# Voltmetr_MEZ.net
KiCad netlist of a schematic drawn in Altium Designer
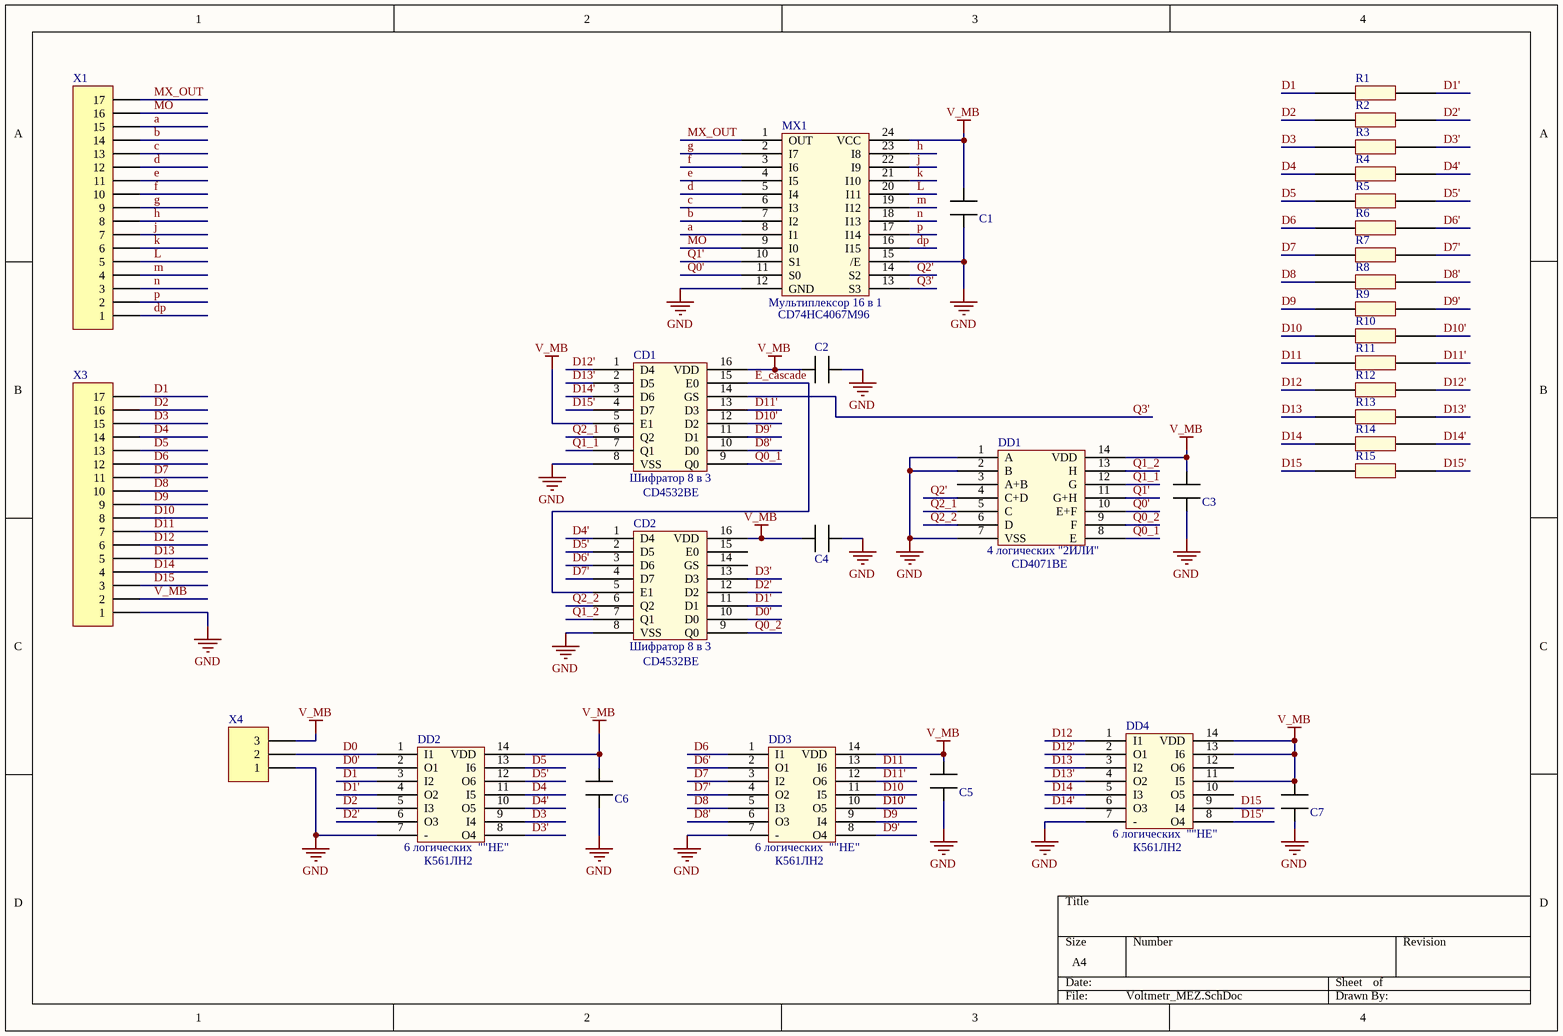
[diagram p0: Voltmetr_MEZ.SchDoc]

(export (version "E")
  (design (tool "Eeschema 10.0.6"))
  (components
    (comp (ref "C1")
      (value "CAP_SMALL")
      (footprint "CAP_SMALL")
      (libsource (lib "vpl_Schlib") (part "CAP_SMALL"))
    )
    (comp (ref "C2")
      (value "CAP_SMALL")
      (footprint "CAP_SMALL")
      (libsource (lib "vpl_Schlib") (part "CAP_SMALL"))
    )
    (comp (ref "C3")
      (value "CAP_SMALL")
      (footprint "CAP_SMALL")
      (libsource (lib "vpl_Schlib") (part "CAP_SMALL"))
    )
    (comp (ref "C4")
      (value "CAP_SMALL")
      (footprint "CAP_SMALL")
      (libsource (lib "vpl_Schlib") (part "CAP_SMALL"))
    )
    (comp (ref "C5")
      (value "CAP_SMALL")
      (footprint "CAP_SMALL")
      (libsource (lib "vpl_Schlib") (part "CAP_SMALL"))
    )
    (comp (ref "C6")
      (value "CAP_SMALL")
      (footprint "CAP_SMALL")
      (libsource (lib "vpl_Schlib") (part "CAP_SMALL"))
    )
    (comp (ref "C7")
      (value "CAP_SMALL")
      (footprint "CAP_SMALL")
      (libsource (lib "vpl_Schlib") (part "CAP_SMALL"))
    )
    (comp (ref "CD1")
      (value "CD4532BE")
      (footprint "DIP16_PANNEL")
      (description "Шифратор приоритетный 8 - 3 [DIP-16]")
      (libsource (lib "msp_SchLib") (part "CD4532BE"))
    )
    (comp (ref "CD2")
      (value "CD4532BE")
      (footprint "DIP16_PANNEL")
      (description "Шифратор приоритетный 8 - 3 [DIP-16]")
      (libsource (lib "msp_SchLib") (part "CD4532BE"))
    )
    (comp (ref "DD1")
      (value "CD4071BE")
      (footprint "Dip14_pannel")
      (description "Четыре логических элемента \"2ИЛИ\", [DIP-14]")
      (libsource (lib "msp_SchLib") (part "CD4071BE"))
    )
    (comp (ref "DD2")
      (value "К561ЛН2")
      (footprint "Dip14_pannel")
      (description "Шесть логических элементов \"HЕ\" (DIP-14)")
      (libsource (lib "msp_SchLib") (part "К561ЛН2"))
    )
    (comp (ref "DD3")
      (value "К561ЛН2")
      (footprint "Dip14_pannel")
      (description "Шесть логических элементов \"HЕ\" (DIP-14)")
      (libsource (lib "msp_SchLib") (part "К561ЛН2"))
    )
    (comp (ref "DD4")
      (value "К561ЛН2")
      (footprint "Dip14_pannel")
      (description "Шесть логических элементов \"HЕ\" (DIP-14)")
      (libsource (lib "msp_SchLib") (part "К561ЛН2"))
    )
    (comp (ref "MX1")
      (value "CD74HC4067M96")
      (footprint "SOIC-24")
      (description "16-и канальный аналоговый мультиплексор/ демультиплексор, [SO-24]")
      (libsource (lib "msp_SchLib") (part "CD74HC4067M96"))
    )
    (comp (ref "R1") (value "resistor") (footprint "RES 0805") (libsource (lib "msp_SchLib") (part "RES")))
    (comp (ref "R2") (value "resistor") (footprint "RES 0805") (libsource (lib "msp_SchLib") (part "RES")))
    (comp (ref "R3") (value "resistor") (footprint "RES 0805") (libsource (lib "msp_SchLib") (part "RES")))
    (comp (ref "R4") (value "resistor") (footprint "RES 0805") (libsource (lib "msp_SchLib") (part "RES")))
    (comp (ref "R5") (value "resistor") (footprint "RES 0805") (libsource (lib "msp_SchLib") (part "RES")))
    (comp (ref "R6") (value "resistor") (footprint "RES 0805") (libsource (lib "msp_SchLib") (part "RES")))
    (comp (ref "R7") (value "resistor") (footprint "RES 0805") (libsource (lib "msp_SchLib") (part "RES")))
    (comp (ref "R8") (value "resistor") (footprint "RES 0805") (libsource (lib "msp_SchLib") (part "RES")))
    (comp (ref "R9") (value "resistor") (footprint "RES 0805") (libsource (lib "msp_SchLib") (part "RES")))
    (comp (ref "R10") (value "resistor") (footprint "RES 0805") (libsource (lib "msp_SchLib") (part "RES")))
    (comp (ref "R11") (value "resistor") (footprint "RES 0805") (libsource (lib "msp_SchLib") (part "RES")))
    (comp (ref "R12") (value "resistor") (footprint "RES 0805") (libsource (lib "msp_SchLib") (part "RES")))
    (comp (ref "R13") (value "resistor") (footprint "RES 0805") (libsource (lib "msp_SchLib") (part "RES")))
    (comp (ref "R14") (value "resistor") (footprint "RES 0805") (libsource (lib "msp_SchLib") (part "RES")))
    (comp (ref "R15") (value "resistor") (footprint "RES 0805") (libsource (lib "msp_SchLib") (part "RES")))
    (comp (ref "X1")
      (value "Header 17")
      (footprint "HDR1X17")
      (description "Header, 17-Pin")
      (fields (field (name "PUBLISHER") "Altium Limited"))
      (libsource (lib "Miscellaneous Connectors") (part "Header 17"))
    )
    (comp (ref "X3")
      (value "Header 17")
      (footprint "HDR1X17")
      (description "Header, 17-Pin")
      (fields (field (name "PUBLISHER") "Altium Limited"))
      (libsource (lib "Miscellaneous Connectors") (part "Header 17"))
    )
    (comp (ref "X4")
      (value "Header 3")
      (footprint "HDR1X3")
      (description "Header, 3-Pin")
      (fields (field (name "PUBLISHER") "Altium Limited"))
      (libsource (lib "Miscellaneous Connectors") (part "Header 3"))
    )
  )
  (nets
    (net (code "2") (name "/D0") (class "Default")
      (node (ref "DD2") (pin "1") (pinfunction "I1_1") (pintype "passive"))
      (node (ref "X4") (pin "2") (pinfunction "2_2") (pintype "passive"))
    )
    (net (code "3") (name "/D0'") (class "Default")
      (node (ref "CD2") (pin "10") (pinfunction "D0_10") (pintype "passive"))
      (node (ref "DD2") (pin "2") (pinfunction "O1_2") (pintype "passive"))
    )
    (net (code "4") (name "/D1") (class "Default")
      (node (ref "DD2") (pin "3") (pinfunction "I2_3") (pintype "passive"))
      (node (ref "R1") (pin "1") (pinfunction "1_1") (pintype "passive"))
      (node (ref "X3") (pin "17") (pinfunction "17_17") (pintype "passive"))
    )
    (net (code "5") (name "/D1'") (class "Default")
      (node (ref "CD2") (pin "11") (pinfunction "D1_11") (pintype "passive"))
      (node (ref "DD2") (pin "4") (pinfunction "O2_4") (pintype "passive"))
      (node (ref "R1") (pin "2") (pinfunction "2_2") (pintype "passive"))
    )
    (net (code "6") (name "/D2") (class "Default")
      (node (ref "DD2") (pin "5") (pinfunction "I3_5") (pintype "passive"))
      (node (ref "R2") (pin "1") (pinfunction "1_1") (pintype "passive"))
      (node (ref "X3") (pin "16") (pinfunction "16_16") (pintype "passive"))
    )
    (net (code "7") (name "/D2'") (class "Default")
      (node (ref "CD2") (pin "12") (pinfunction "D2_12") (pintype "passive"))
      (node (ref "DD2") (pin "6") (pinfunction "O3_6") (pintype "passive"))
      (node (ref "R2") (pin "2") (pinfunction "2_2") (pintype "passive"))
    )
    (net (code "8") (name "/D3") (class "Default")
      (node (ref "DD2") (pin "9") (pinfunction "I4_9") (pintype "passive"))
      (node (ref "R3") (pin "1") (pinfunction "1_1") (pintype "passive"))
      (node (ref "X3") (pin "15") (pinfunction "15_15") (pintype "passive"))
    )
    (net (code "9") (name "/D3'") (class "Default")
      (node (ref "CD2") (pin "13") (pinfunction "D3_13") (pintype "passive"))
      (node (ref "DD2") (pin "8") (pinfunction "O4_8") (pintype "passive"))
      (node (ref "R3") (pin "2") (pinfunction "2_2") (pintype "passive"))
    )
    (net (code "10") (name "/D4") (class "Default")
      (node (ref "DD2") (pin "11") (pinfunction "I5_11") (pintype "passive"))
      (node (ref "R4") (pin "1") (pinfunction "1_1") (pintype "passive"))
      (node (ref "X3") (pin "14") (pinfunction "14_14") (pintype "passive"))
    )
    (net (code "11") (name "/D4'") (class "Default")
      (node (ref "CD2") (pin "1") (pinfunction "D4_1") (pintype "passive"))
      (node (ref "DD2") (pin "10") (pinfunction "O5_10") (pintype "passive"))
      (node (ref "R4") (pin "2") (pinfunction "2_2") (pintype "passive"))
    )
    (net (code "12") (name "/D5") (class "Default")
      (node (ref "DD2") (pin "13") (pinfunction "I6_13") (pintype "passive"))
      (node (ref "R5") (pin "1") (pinfunction "1_1") (pintype "passive"))
      (node (ref "X3") (pin "13") (pinfunction "13_13") (pintype "passive"))
    )
    (net (code "13") (name "/D5'") (class "Default")
      (node (ref "CD2") (pin "2") (pinfunction "D5_2") (pintype "passive"))
      (node (ref "DD2") (pin "12") (pinfunction "O6_12") (pintype "passive"))
      (node (ref "R5") (pin "2") (pinfunction "2_2") (pintype "passive"))
    )
    (net (code "14") (name "/D6") (class "Default")
      (node (ref "DD3") (pin "1") (pinfunction "I1_1") (pintype "passive"))
      (node (ref "R6") (pin "1") (pinfunction "1_1") (pintype "passive"))
      (node (ref "X3") (pin "12") (pinfunction "12_12") (pintype "passive"))
    )
    (net (code "15") (name "/D6'") (class "Default")
      (node (ref "CD2") (pin "3") (pinfunction "D6_3") (pintype "passive"))
      (node (ref "DD3") (pin "2") (pinfunction "O1_2") (pintype "passive"))
      (node (ref "R6") (pin "2") (pinfunction "2_2") (pintype "passive"))
    )
    (net (code "16") (name "/D7") (class "Default")
      (node (ref "DD3") (pin "3") (pinfunction "I2_3") (pintype "passive"))
      (node (ref "R7") (pin "1") (pinfunction "1_1") (pintype "passive"))
      (node (ref "X3") (pin "11") (pinfunction "11_11") (pintype "passive"))
    )
    (net (code "17") (name "/D7'") (class "Default")
      (node (ref "CD2") (pin "4") (pinfunction "D7_4") (pintype "passive"))
      (node (ref "DD3") (pin "4") (pinfunction "O2_4") (pintype "passive"))
      (node (ref "R7") (pin "2") (pinfunction "2_2") (pintype "passive"))
    )
    (net (code "18") (name "/D8") (class "Default")
      (node (ref "DD3") (pin "5") (pinfunction "I3_5") (pintype "passive"))
      (node (ref "R8") (pin "1") (pinfunction "1_1") (pintype "passive"))
      (node (ref "X3") (pin "10") (pinfunction "10_10") (pintype "passive"))
    )
    (net (code "19") (name "/D8'") (class "Default")
      (node (ref "CD1") (pin "10") (pinfunction "D0_10") (pintype "passive"))
      (node (ref "DD3") (pin "6") (pinfunction "O3_6") (pintype "passive"))
      (node (ref "R8") (pin "2") (pinfunction "2_2") (pintype "passive"))
    )
    (net (code "20") (name "/D9") (class "Default")
      (node (ref "DD3") (pin "9") (pinfunction "I4_9") (pintype "passive"))
      (node (ref "R9") (pin "1") (pinfunction "1_1") (pintype "passive"))
      (node (ref "X3") (pin "9") (pinfunction "9_9") (pintype "passive"))
    )
    (net (code "21") (name "/D9'") (class "Default")
      (node (ref "CD1") (pin "11") (pinfunction "D1_11") (pintype "passive"))
      (node (ref "DD3") (pin "8") (pinfunction "O4_8") (pintype "passive"))
      (node (ref "R9") (pin "2") (pinfunction "2_2") (pintype "passive"))
    )
    (net (code "22") (name "/D10") (class "Default")
      (node (ref "DD3") (pin "11") (pinfunction "I5_11") (pintype "passive"))
      (node (ref "R10") (pin "1") (pinfunction "1_1") (pintype "passive"))
      (node (ref "X3") (pin "8") (pinfunction "8_8") (pintype "passive"))
    )
    (net (code "23") (name "/D10'") (class "Default")
      (node (ref "CD1") (pin "12") (pinfunction "D2_12") (pintype "passive"))
      (node (ref "DD3") (pin "10") (pinfunction "O5_10") (pintype "passive"))
      (node (ref "R10") (pin "2") (pinfunction "2_2") (pintype "passive"))
    )
    (net (code "24") (name "/D11") (class "Default")
      (node (ref "DD3") (pin "13") (pinfunction "I6_13") (pintype "passive"))
      (node (ref "R11") (pin "1") (pinfunction "1_1") (pintype "passive"))
      (node (ref "X3") (pin "7") (pinfunction "7_7") (pintype "passive"))
    )
    (net (code "25") (name "/D11'") (class "Default")
      (node (ref "CD1") (pin "13") (pinfunction "D3_13") (pintype "passive"))
      (node (ref "DD3") (pin "12") (pinfunction "O6_12") (pintype "passive"))
      (node (ref "R11") (pin "2") (pinfunction "2_2") (pintype "passive"))
    )
    (net (code "26") (name "/D12") (class "Default")
      (node (ref "DD4") (pin "1") (pinfunction "I1_1") (pintype "passive"))
      (node (ref "R12") (pin "1") (pinfunction "1_1") (pintype "passive"))
      (node (ref "X3") (pin "6") (pinfunction "6_6") (pintype "passive"))
    )
    (net (code "27") (name "/D12'") (class "Default")
      (node (ref "CD1") (pin "1") (pinfunction "D4_1") (pintype "passive"))
      (node (ref "DD4") (pin "2") (pinfunction "O1_2") (pintype "passive"))
      (node (ref "R12") (pin "2") (pinfunction "2_2") (pintype "passive"))
    )
    (net (code "28") (name "/D13") (class "Default")
      (node (ref "DD4") (pin "3") (pinfunction "I2_3") (pintype "passive"))
      (node (ref "R13") (pin "1") (pinfunction "1_1") (pintype "passive"))
      (node (ref "X3") (pin "5") (pinfunction "5_5") (pintype "passive"))
    )
    (net (code "29") (name "/D13'") (class "Default")
      (node (ref "CD1") (pin "2") (pinfunction "D5_2") (pintype "passive"))
      (node (ref "DD4") (pin "4") (pinfunction "O2_4") (pintype "passive"))
      (node (ref "R13") (pin "2") (pinfunction "2_2") (pintype "passive"))
    )
    (net (code "30") (name "/D14") (class "Default")
      (node (ref "DD4") (pin "5") (pinfunction "I3_5") (pintype "passive"))
      (node (ref "R14") (pin "1") (pinfunction "1_1") (pintype "passive"))
      (node (ref "X3") (pin "4") (pinfunction "4_4") (pintype "passive"))
    )
    (net (code "31") (name "/D14'") (class "Default")
      (node (ref "CD1") (pin "3") (pinfunction "D6_3") (pintype "passive"))
      (node (ref "DD4") (pin "6") (pinfunction "O3_6") (pintype "passive"))
      (node (ref "R14") (pin "2") (pinfunction "2_2") (pintype "passive"))
    )
    (net (code "32") (name "/D15") (class "Default")
      (node (ref "DD4") (pin "9") (pinfunction "I4_9") (pintype "passive"))
      (node (ref "R15") (pin "1") (pinfunction "1_1") (pintype "passive"))
      (node (ref "X3") (pin "3") (pinfunction "3_3") (pintype "passive"))
    )
    (net (code "33") (name "/D15'") (class "Default")
      (node (ref "CD1") (pin "4") (pinfunction "D7_4") (pintype "passive"))
      (node (ref "DD4") (pin "8") (pinfunction "O4_8") (pintype "passive"))
      (node (ref "R15") (pin "2") (pinfunction "2_2") (pintype "passive"))
    )
    (net (code "34") (name "/E_cascade") (class "Default")
      (node (ref "CD1") (pin "15") (pinfunction "E0_15") (pintype "passive"))
      (node (ref "CD2") (pin "5") (pinfunction "E1_5") (pintype "passive"))
    )
    (net (code "35") (name "/L") (class "Default")
      (node (ref "MX1") (pin "20") (pinfunction "I11_20") (pintype "passive"))
      (node (ref "X1") (pin "5") (pinfunction "5_5") (pintype "passive"))
    )
    (net (code "36") (name "/MX_OUT") (class "Default")
      (node (ref "MX1") (pin "1") (pinfunction "OUT_1") (pintype "passive"))
      (node (ref "X1") (pin "17") (pinfunction "17_17") (pintype "passive"))
    )
    (net (code "37") (name "/Q0'") (class "Default")
      (node (ref "DD1") (pin "10") (pinfunction "E+F_10") (pintype "passive"))
      (node (ref "MX1") (pin "11") (pinfunction "S0_11") (pintype "passive"))
    )
    (net (code "38") (name "/Q0_1") (class "Default")
      (node (ref "CD1") (pin "9") (pinfunction "Q0_9") (pintype "passive"))
      (node (ref "DD1") (pin "8") (pinfunction "E_8") (pintype "passive"))
    )
    (net (code "39") (name "/Q0_2") (class "Default")
      (node (ref "CD2") (pin "9") (pinfunction "Q0_9") (pintype "passive"))
      (node (ref "DD1") (pin "9") (pinfunction "F_9") (pintype "passive"))
    )
    (net (code "40") (name "/Q1'") (class "Default")
      (node (ref "DD1") (pin "11") (pinfunction "G+H_11") (pintype "passive"))
      (node (ref "MX1") (pin "10") (pinfunction "S1_10") (pintype "passive"))
    )
    (net (code "41") (name "/Q1_1") (class "Default")
      (node (ref "CD1") (pin "7") (pinfunction "Q1_7") (pintype "passive"))
      (node (ref "DD1") (pin "12") (pinfunction "G_12") (pintype "passive"))
    )
    (net (code "42") (name "/Q1_2") (class "Default")
      (node (ref "CD2") (pin "7") (pinfunction "Q1_7") (pintype "passive"))
      (node (ref "DD1") (pin "13") (pinfunction "H_13") (pintype "passive"))
    )
    (net (code "43") (name "/Q2'") (class "Default")
      (node (ref "DD1") (pin "4") (pinfunction "C+D_4") (pintype "passive"))
      (node (ref "MX1") (pin "14") (pinfunction "S2_14") (pintype "passive"))
    )
    (net (code "44") (name "/Q2_1") (class "Default")
      (node (ref "CD1") (pin "6") (pinfunction "Q2_6") (pintype "passive"))
      (node (ref "DD1") (pin "5") (pinfunction "C_5") (pintype "passive"))
    )
    (net (code "45") (name "/Q2_2") (class "Default")
      (node (ref "CD2") (pin "6") (pinfunction "Q2_6") (pintype "passive"))
      (node (ref "DD1") (pin "6") (pinfunction "D_6") (pintype "passive"))
    )
    (net (code "46") (name "/Q3'") (class "Default")
      (node (ref "CD1") (pin "14") (pinfunction "GS_14") (pintype "passive"))
      (node (ref "MX1") (pin "13") (pinfunction "S3_13") (pintype "passive"))
    )
    (net (code "47") (name "/a") (class "Default")
      (node (ref "MX1") (pin "8") (pinfunction "I1_8") (pintype "passive"))
      (node (ref "X1") (pin "15") (pinfunction "15_15") (pintype "passive"))
    )
    (net (code "48") (name "/b") (class "Default")
      (node (ref "MX1") (pin "7") (pinfunction "I2_7") (pintype "passive"))
      (node (ref "X1") (pin "14") (pinfunction "14_14") (pintype "passive"))
    )
    (net (code "49") (name "/c") (class "Default")
      (node (ref "MX1") (pin "6") (pinfunction "I3_6") (pintype "passive"))
      (node (ref "X1") (pin "13") (pinfunction "13_13") (pintype "passive"))
    )
    (net (code "50") (name "/d") (class "Default")
      (node (ref "MX1") (pin "5") (pinfunction "I4_5") (pintype "passive"))
      (node (ref "X1") (pin "12") (pinfunction "12_12") (pintype "passive"))
    )
    (net (code "51") (name "/dp") (class "Default")
      (node (ref "MX1") (pin "16") (pinfunction "I15_16") (pintype "passive"))
      (node (ref "X1") (pin "1") (pinfunction "1_1") (pintype "passive"))
    )
    (net (code "52") (name "/e") (class "Default")
      (node (ref "MX1") (pin "4") (pinfunction "I5_4") (pintype "passive"))
      (node (ref "X1") (pin "11") (pinfunction "11_11") (pintype "passive"))
    )
    (net (code "53") (name "/f") (class "Default")
      (node (ref "MX1") (pin "3") (pinfunction "I6_3") (pintype "passive"))
      (node (ref "X1") (pin "10") (pinfunction "10_10") (pintype "passive"))
    )
    (net (code "54") (name "/g") (class "Default")
      (node (ref "MX1") (pin "2") (pinfunction "I7_2") (pintype "passive"))
      (node (ref "X1") (pin "9") (pinfunction "9_9") (pintype "passive"))
    )
    (net (code "55") (name "/h") (class "Default")
      (node (ref "MX1") (pin "23") (pinfunction "I8_23") (pintype "passive"))
      (node (ref "X1") (pin "8") (pinfunction "8_8") (pintype "passive"))
    )
    (net (code "56") (name "/j") (class "Default")
      (node (ref "MX1") (pin "22") (pinfunction "I9_22") (pintype "passive"))
      (node (ref "X1") (pin "7") (pinfunction "7_7") (pintype "passive"))
    )
    (net (code "57") (name "/k") (class "Default")
      (node (ref "MX1") (pin "21") (pinfunction "I10_21") (pintype "passive"))
      (node (ref "X1") (pin "6") (pinfunction "6_6") (pintype "passive"))
    )
    (net (code "58") (name "/m") (class "Default")
      (node (ref "MX1") (pin "19") (pinfunction "I12_19") (pintype "passive"))
      (node (ref "X1") (pin "4") (pinfunction "4_4") (pintype "passive"))
    )
    (net (code "59") (name "/n") (class "Default")
      (node (ref "MX1") (pin "18") (pinfunction "I13_18") (pintype "passive"))
      (node (ref "X1") (pin "3") (pinfunction "3_3") (pintype "passive"))
    )
    (net (code "60") (name "/p") (class "Default")
      (node (ref "MX1") (pin "17") (pinfunction "I14_17") (pintype "passive"))
      (node (ref "X1") (pin "2") (pinfunction "2_2") (pintype "passive"))
    )
    (net (code "61") (name "/~{MO}") (class "Default")
      (node (ref "MX1") (pin "9") (pinfunction "I0_9") (pintype "passive"))
      (node (ref "X1") (pin "16") (pinfunction "16_16") (pintype "passive"))
    )
    (net (code "62") (name "GND") (class "Default")
      (node (ref "C1") (pin "1") (pinfunction "1_1") (pintype "passive"))
      (node (ref "C2") (pin "2") (pinfunction "2_2") (pintype "passive"))
      (node (ref "C3") (pin "1") (pinfunction "1_1") (pintype "passive"))
      (node (ref "C4") (pin "1") (pinfunction "1_1") (pintype "passive"))
      (node (ref "C5") (pin "1") (pinfunction "1_1") (pintype "passive"))
      (node (ref "C6") (pin "1") (pinfunction "1_1") (pintype "passive"))
      (node (ref "C7") (pin "1") (pinfunction "1_1") (pintype "passive"))
      (node (ref "CD1") (pin "8") (pinfunction "VSS_8") (pintype "passive"))
      (node (ref "CD2") (pin "8") (pinfunction "VSS_8") (pintype "passive"))
      (node (ref "DD1") (pin "1") (pinfunction "A_1") (pintype "passive"))
      (node (ref "DD1") (pin "2") (pinfunction "B_2") (pintype "passive"))
      (node (ref "DD1") (pin "7") (pinfunction "VSS_7") (pintype "passive"))
      (node (ref "DD2") (pin "7") (pinfunction "-_7") (pintype "passive"))
      (node (ref "DD3") (pin "7") (pinfunction "-_7") (pintype "passive"))
      (node (ref "DD4") (pin "7") (pinfunction "-_7") (pintype "passive"))
      (node (ref "MX1") (pin "12") (pinfunction "GND_12") (pintype "passive"))
      (node (ref "MX1") (pin "15") (pinfunction "/E_15") (pintype "passive"))
      (node (ref "X3") (pin "1") (pinfunction "1_1") (pintype "passive"))
      (node (ref "X4") (pin "1") (pinfunction "1_1") (pintype "passive"))
    )
    (net (code "63") (name "V_MB") (class "Default")
      (node (ref "C1") (pin "2") (pinfunction "2_2") (pintype "passive"))
      (node (ref "C2") (pin "1") (pinfunction "1_1") (pintype "passive"))
      (node (ref "C3") (pin "2") (pinfunction "2_2") (pintype "passive"))
      (node (ref "C4") (pin "2") (pinfunction "2_2") (pintype "passive"))
      (node (ref "C5") (pin "2") (pinfunction "2_2") (pintype "passive"))
      (node (ref "C6") (pin "2") (pinfunction "2_2") (pintype "passive"))
      (node (ref "C7") (pin "2") (pinfunction "2_2") (pintype "passive"))
      (node (ref "CD1") (pin "16") (pinfunction "VDD_16") (pintype "passive"))
      (node (ref "CD1") (pin "5") (pinfunction "E1_5") (pintype "passive"))
      (node (ref "CD2") (pin "16") (pinfunction "VDD_16") (pintype "passive"))
      (node (ref "DD1") (pin "14") (pinfunction "VDD_14") (pintype "passive"))
      (node (ref "DD2") (pin "14") (pinfunction "VDD_14") (pintype "passive"))
      (node (ref "DD3") (pin "14") (pinfunction "VDD_14") (pintype "passive"))
      (node (ref "DD4") (pin "11") (pinfunction "I5_11") (pintype "passive"))
      (node (ref "DD4") (pin "13") (pinfunction "I6_13") (pintype "passive"))
      (node (ref "DD4") (pin "14") (pinfunction "VDD_14") (pintype "passive"))
      (node (ref "MX1") (pin "24") (pinfunction "VCC_24") (pintype "passive"))
      (node (ref "X3") (pin "2") (pinfunction "2_2") (pintype "passive"))
      (node (ref "X4") (pin "3") (pinfunction "3_3") (pintype "passive"))
    )
    (net (code "64") (name "unconnected-(CD2-E0-Pad15)") (class "Default")
      (node (ref "CD2") (pin "15") (pinfunction "E0_15") (pintype "passive"))
    )
    (net (code "65") (name "unconnected-(CD2-GS-Pad14)") (class "Default")
      (node (ref "CD2") (pin "14") (pinfunction "GS_14") (pintype "passive"))
    )
    (net (code "66") (name "unconnected-(DD1-A+B-Pad3)") (class "Default")
      (node (ref "DD1") (pin "3") (pinfunction "A+B_3") (pintype "passive"))
    )
    (net (code "67") (name "unconnected-(DD4-O5-Pad10)") (class "Default")
      (node (ref "DD4") (pin "10") (pinfunction "O5_10") (pintype "passive"))
    )
    (net (code "68") (name "unconnected-(DD4-O6-Pad12)") (class "Default")
      (node (ref "DD4") (pin "12") (pinfunction "O6_12") (pintype "passive"))
    )
  )
)
